# uv-dosimeter-guva-op-amp-mk-1_2.net
KiCad netlist of a schematic drawn in EAGLE
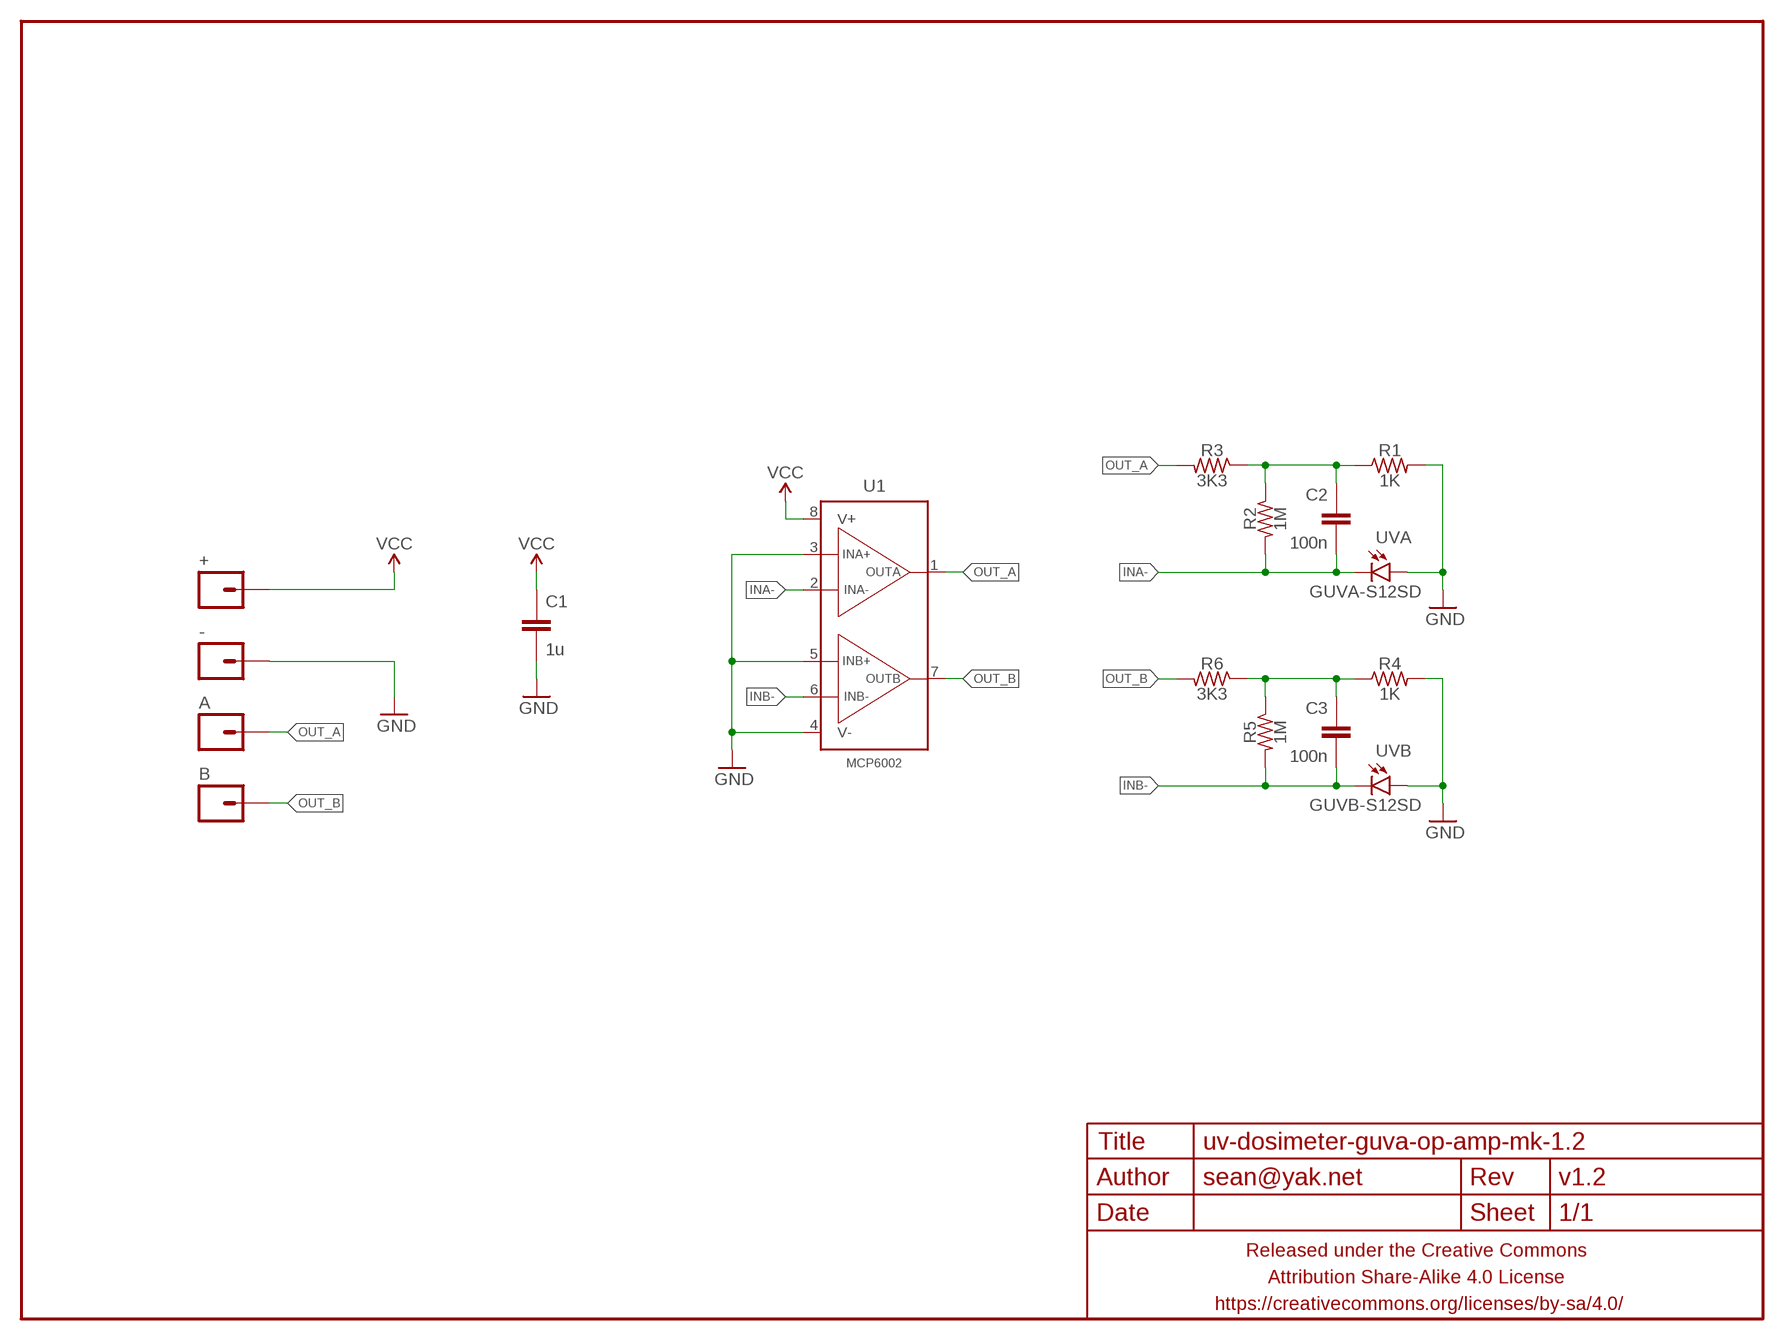
[diagram p0: schematic, sheet 1]

(export (version "E")
  (design (tool "Eeschema 10.0.6"))
  (components
    (comp (ref "+")
      (value "M01PTH")
      (footprint "eagle-import:1X01")
      (libsource (lib "eagle-import") (part "M01PTH"))
    )
    (comp (ref "-")
      (value "M01PTH")
      (footprint "eagle-import:1X01")
      (libsource (lib "eagle-import") (part "M01PTH"))
    )
    (comp (ref "A")
      (value "M01PTH")
      (footprint "eagle-import:1X01")
      (libsource (lib "eagle-import") (part "M01PTH"))
    )
    (comp (ref "B")
      (value "M01PTH")
      (footprint "eagle-import:1X01")
      (libsource (lib "eagle-import") (part "M01PTH"))
    )
    (comp (ref "C1")
      (value "1u")
      (footprint "eagle-import:C0603")
      (libsource (lib "eagle-import") (part "CAPACITOR-CERAMICC0603"))
    )
    (comp (ref "C2")
      (value "100n")
      (footprint "eagle-import:C0603")
      (libsource (lib "eagle-import") (part "CAPACITOR-CERAMICC0603"))
    )
    (comp (ref "C3")
      (value "100n")
      (footprint "eagle-import:C0603")
      (libsource (lib "eagle-import") (part "CAPACITOR-CERAMICC0603"))
    )
    (comp (ref "FRAME1")
      (value "FRAME-LETTERNO_PACKAGE")
      (footprint "eagle-import:DUMMY")
      (fields (field (name "DESIGNER") "sean@yak.net") (field (name "VERSION") "v1.2"))
      (libsource (lib "eagle-import") (part "FRAME-LETTERNO_PACKAGE"))
    )
    (comp (ref "R1")
      (value "1K")
      (footprint "eagle-import:R0603")
      (libsource (lib "eagle-import") (part "RESISTORR0603"))
    )
    (comp (ref "R2")
      (value "1M")
      (footprint "eagle-import:R0603")
      (libsource (lib "eagle-import") (part "RESISTORR0603"))
    )
    (comp (ref "R3")
      (value "3K3")
      (footprint "eagle-import:R0603")
      (libsource (lib "eagle-import") (part "RESISTORR0603"))
    )
    (comp (ref "R4")
      (value "1K")
      (footprint "eagle-import:R0603")
      (libsource (lib "eagle-import") (part "RESISTORR0603"))
    )
    (comp (ref "R5")
      (value "1M")
      (footprint "eagle-import:R0603")
      (libsource (lib "eagle-import") (part "RESISTORR0603"))
    )
    (comp (ref "R6")
      (value "3K3")
      (footprint "eagle-import:R0603")
      (libsource (lib "eagle-import") (part "RESISTORR0603"))
    )
    (comp (ref "U1")
      (value "MCP6002")
      (footprint "eagle-import:SO08")
      (libsource (lib "eagle-import") (part "MCP6002SOIC"))
    )
    (comp (ref "UVA")
      (value "GUVA-S12SD")
      (footprint "eagle-import:LED3528")
      (libsource (lib "eagle-import") (part "GUVA-S12SDLED3528"))
    )
    (comp (ref "UVB")
      (value "GUVB-S12SD")
      (footprint "eagle-import:LED3528")
      (libsource (lib "eagle-import") (part "GUVA-S12SDLED3528"))
    )
  )
  (nets
    (net (code "1") (name "GND") (class "Default")
      (node (ref "-") (pin "1") (pinfunction "1_1") (pintype "passive"))
      (node (ref "C1") (pin "2") (pinfunction "2_2") (pintype "passive"))
      (node (ref "R1") (pin "2") (pinfunction "2_2") (pintype "passive"))
      (node (ref "R4") (pin "2") (pinfunction "2_2") (pintype "passive"))
      (node (ref "U1") (pin "3") (pinfunction "INA+_3") (pintype "input"))
      (node (ref "U1") (pin "4") (pinfunction "V-_4") (pintype "power_in"))
      (node (ref "U1") (pin "5") (pinfunction "INB+_5") (pintype "input"))
      (node (ref "UVA") (pin "A") (pinfunction "A_A") (pintype "passive"))
      (node (ref "UVB") (pin "A") (pinfunction "A_A") (pintype "passive"))
    )
    (net (code "2") (name "INA-") (class "Default")
      (node (ref "C2") (pin "2") (pinfunction "2_2") (pintype "passive"))
      (node (ref "R2") (pin "2") (pinfunction "2_2") (pintype "passive"))
      (node (ref "U1") (pin "2") (pinfunction "INA-_2") (pintype "input"))
      (node (ref "UVA") (pin "K") (pinfunction "C_K") (pintype "passive"))
    )
    (net (code "3") (name "INB-") (class "Default")
      (node (ref "C3") (pin "2") (pinfunction "2_2") (pintype "passive"))
      (node (ref "R5") (pin "2") (pinfunction "2_2") (pintype "passive"))
      (node (ref "U1") (pin "6") (pinfunction "INB-_6") (pintype "input"))
      (node (ref "UVB") (pin "K") (pinfunction "C_K") (pintype "passive"))
    )
    (net (code "4") (name "Net-(C2-Pad1)") (class "Default")
      (node (ref "C2") (pin "1") (pinfunction "1_1") (pintype "passive"))
      (node (ref "R1") (pin "1") (pinfunction "1_1") (pintype "passive"))
      (node (ref "R2") (pin "1") (pinfunction "1_1") (pintype "passive"))
      (node (ref "R3") (pin "1") (pinfunction "1_1") (pintype "passive"))
    )
    (net (code "5") (name "Net-(C3-Pad1)") (class "Default")
      (node (ref "C3") (pin "1") (pinfunction "1_1") (pintype "passive"))
      (node (ref "R4") (pin "1") (pinfunction "1_1") (pintype "passive"))
      (node (ref "R5") (pin "1") (pinfunction "1_1") (pintype "passive"))
      (node (ref "R6") (pin "1") (pinfunction "1_1") (pintype "passive"))
    )
    (net (code "6") (name "OUT_A") (class "Default")
      (node (ref "A") (pin "1") (pinfunction "1_1") (pintype "passive"))
      (node (ref "R3") (pin "2") (pinfunction "2_2") (pintype "passive"))
      (node (ref "U1") (pin "1") (pinfunction "OUTA_1") (pintype "output"))
    )
    (net (code "7") (name "OUT_B") (class "Default")
      (node (ref "B") (pin "1") (pinfunction "1_1") (pintype "passive"))
      (node (ref "R6") (pin "2") (pinfunction "2_2") (pintype "passive"))
      (node (ref "U1") (pin "7") (pinfunction "OUTB_7") (pintype "output"))
    )
    (net (code "8") (name "VCC") (class "Default")
      (node (ref "+") (pin "1") (pinfunction "1_1") (pintype "passive"))
      (node (ref "C1") (pin "1") (pinfunction "1_1") (pintype "passive"))
      (node (ref "U1") (pin "8") (pinfunction "V+_8") (pintype "power_in"))
    )
  )
)
